# RC.net
KiCad netlist of a schematic drawn in EAGLE
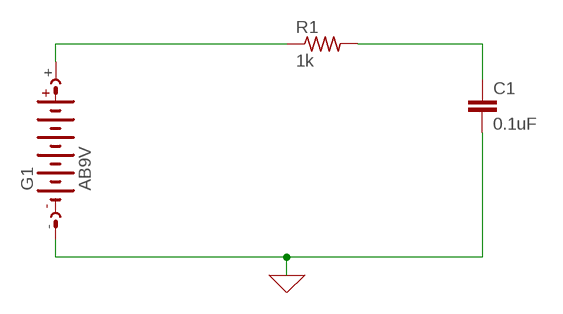
[diagram p0: schematic, sheet 1]

(export (version "E")
  (design (tool "Eeschema 10.0.6"))
  (components
    (comp (ref "C1")
      (value "0.1uF")
      (footprint "eagle-import:0402")
      (libsource (lib "eagle-import") (part "0.1UF-0402-6.3V-10%-X7R"))
    )
    (comp (ref "G1")
      (value "AB9V")
      (footprint "eagle-import:AB9V")
      (libsource (lib "eagle-import") (part "AB9V"))
    )
    (comp (ref "R1")
      (value "1k")
      (footprint "eagle-import:0204V")
      (libsource (lib "eagle-import") (part "R-US_0204/2V"))
    )
  )
  (nets
    (net (code "1") (name "GND") (class "Default")
      (node (ref "C1") (pin "2") (pinfunction "2_2") (pintype "passive"))
      (node (ref "G1") (pin "-") (pinfunction "-_-") (pintype "passive"))
    )
    (net (code "2") (name "Net-(C1-Pad1)") (class "Default")
      (node (ref "C1") (pin "1") (pinfunction "1_1") (pintype "passive"))
      (node (ref "R1") (pin "2") (pinfunction "2_2") (pintype "passive"))
    )
    (net (code "3") (name "Net-(G1-Pad+)") (class "Default")
      (node (ref "G1") (pin "+") (pinfunction "+_+") (pintype "passive"))
      (node (ref "R1") (pin "1") (pinfunction "1_1") (pintype "passive"))
    )
  )
)
